# Modulo_de_isola_o_AC.net
KiCad netlist of a schematic drawn in Altium Designer
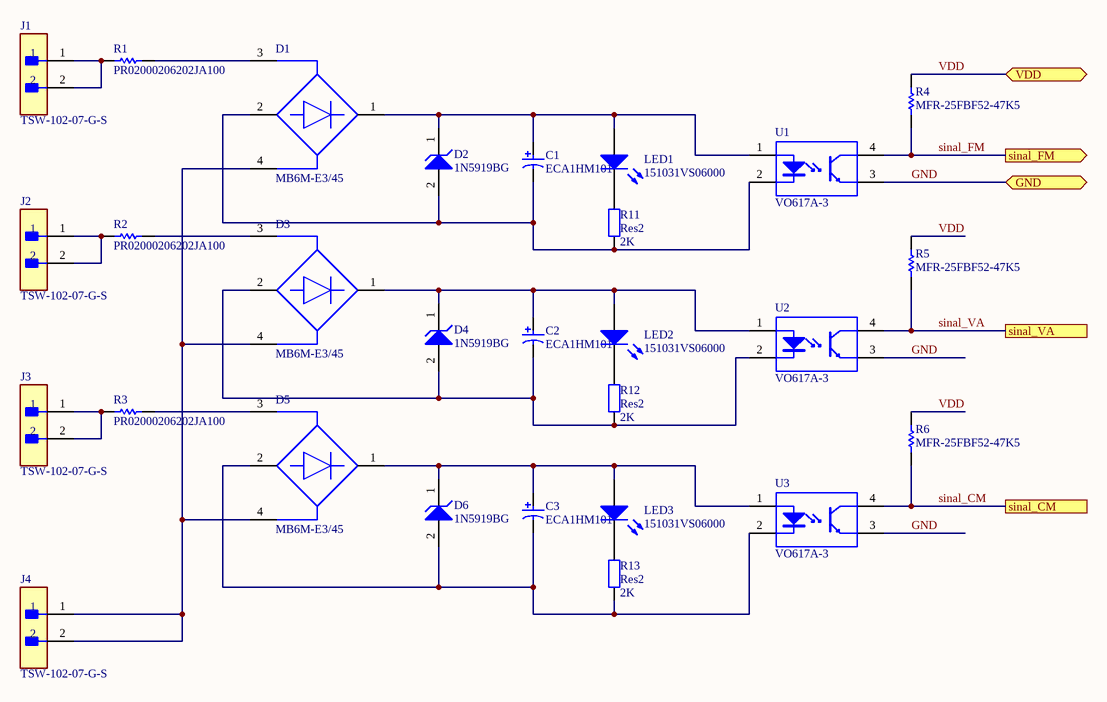
[diagram p0: Modulo de isolação AC.SchDoc]

(export (version "E")
  (design (tool "Eeschema 10.0.6"))
  (components
    (comp (ref "C1")
      (value "ECA1HM101")
      (footprint "CAPPR65-350-1150X800X1250")
      (description "Aluminum Electrolytic Capacitor, 100 uF, +/- 20%, 50 V, -40 to 85 degC, 2-Pin THD, RoHS, Bulk")
      (fields (field (name "MANUFACTURER") "Panasonic") (field (name "VOLTAGE") "50V"))
      (libsource (lib "Altium Content Vault") (part "CAP-P-2"))
    )
    (comp (ref "C2")
      (value "ECA1HM101")
      (footprint "CAPPR65-350-1150X800X1250")
      (description "Aluminum Electrolytic Capacitor, 100 uF, +/- 20%, 50 V, -40 to 85 degC, 2-Pin THD, RoHS, Bulk")
      (fields (field (name "MANUFACTURER") "Panasonic") (field (name "VOLTAGE") "50V"))
      (libsource (lib "Altium Content Vault") (part "CAP-P-2"))
    )
    (comp (ref "C3")
      (value "ECA1HM101")
      (footprint "CAPPR65-350-1150X800X1250")
      (description "Aluminum Electrolytic Capacitor, 100 uF, +/- 20%, 50 V, -40 to 85 degC, 2-Pin THD, RoHS, Bulk")
      (fields (field (name "MANUFACTURER") "Panasonic") (field (name "VOLTAGE") "50V"))
      (libsource (lib "Altium Content Vault") (part "CAP-P-2"))
    )
    (comp (ref "D1")
      (value "MB6M-E3/45")
      (footprint "FP-MB6M-E3-45-MFG")
      (description "BRIDGE RECT 1P 600V 500MA MBM")
      (libsource (lib "Altium Content Vault") (part "8d9836cf8c3bf52151cda99db45db6a"))
    )
    (comp (ref "D2")
      (value "1N5919BG")
      (footprint "ONSC-AXIAL_LEAD-2-59-10_P")
      (description "3 W Zener Voltage Regulator, 2-Pin Axial_Lead, Pb-Free, Bulk Box")
      (fields (field (name "MANUFACTURER") "On Semiconductor"))
      (libsource (lib "Altium Content Vault") (part "ONSC-K1A2-2"))
    )
    (comp (ref "D3")
      (value "MB6M-E3/45")
      (footprint "FP-MB6M-E3-45-MFG")
      (description "BRIDGE RECT 1P 600V 500MA MBM")
      (libsource (lib "Altium Content Vault") (part "8d9836cf8c3bf52151cda99db45db6a"))
    )
    (comp (ref "D4")
      (value "1N5919BG")
      (footprint "ONSC-AXIAL_LEAD-2-59-10_P")
      (description "3 W Zener Voltage Regulator, 2-Pin Axial_Lead, Pb-Free, Bulk Box")
      (fields (field (name "MANUFACTURER") "On Semiconductor"))
      (libsource (lib "Altium Content Vault") (part "ONSC-K1A2-2"))
    )
    (comp (ref "D5")
      (value "MB6M-E3/45")
      (footprint "FP-MB6M-E3-45-MFG")
      (description "BRIDGE RECT 1P 600V 500MA MBM")
      (libsource (lib "Altium Content Vault") (part "8d9836cf8c3bf52151cda99db45db6a"))
    )
    (comp (ref "D6")
      (value "1N5919BG")
      (footprint "ONSC-AXIAL_LEAD-2-59-10_P")
      (description "3 W Zener Voltage Regulator, 2-Pin Axial_Lead, Pb-Free, Bulk Box")
      (fields (field (name "MANUFACTURER") "On Semiconductor"))
      (libsource (lib "Altium Content Vault") (part "ONSC-K1A2-2"))
    )
    (comp (ref "J1")
      (value "TSW-102-07-G-S")
      (footprint "FP-TSW-102-07-G-S-MFG")
      (description "CONN HEADER VERT 2POS 2.54MM")
      (fields
        (field (name "MANUFACTURER") "Samtec")
        (field (name "OCTOPART") "https://octopart.com/tsw-102-07-g-s-samtec-272197")
      )
      (libsource (lib "Altium Content Vault") (part "3bc925449376181038e59eaffc5286c"))
    )
    (comp (ref "J2")
      (value "TSW-102-07-G-S")
      (footprint "FP-TSW-102-07-G-S-MFG")
      (description "CONN HEADER VERT 2POS 2.54MM")
      (fields
        (field (name "MANUFACTURER") "Samtec")
        (field (name "OCTOPART") "https://octopart.com/tsw-102-07-g-s-samtec-272197")
      )
      (libsource (lib "Altium Content Vault") (part "3bc925449376181038e59eaffc5286c"))
    )
    (comp (ref "J3")
      (value "TSW-102-07-G-S")
      (footprint "FP-TSW-102-07-G-S-MFG")
      (description "CONN HEADER VERT 2POS 2.54MM")
      (fields
        (field (name "MANUFACTURER") "Samtec")
        (field (name "OCTOPART") "https://octopart.com/tsw-102-07-g-s-samtec-272197")
      )
      (libsource (lib "Altium Content Vault") (part "3bc925449376181038e59eaffc5286c"))
    )
    (comp (ref "J4")
      (value "TSW-102-07-G-S")
      (footprint "FP-TSW-102-07-G-S-MFG")
      (description "CONN HEADER VERT 2POS 2.54MM")
      (fields
        (field (name "MANUFACTURER") "Samtec")
        (field (name "OCTOPART") "https://octopart.com/tsw-102-07-g-s-samtec-272197")
      )
      (libsource (lib "Altium Content Vault") (part "3bc925449376181038e59eaffc5286c"))
    )
    (comp (ref "LED1")
      (value "151031VS06000")
      (footprint "Type 3mm")
      (description "THT LED round mono-color color lens, WL-TMRC , Bright Green")
      (fields (field (name "MANUFACTURER") "Wuerth Elektronik"))
      (libsource (lib "Altium Content Vault") (part "WE-LED_K1A2-2"))
    )
    (comp (ref "LED2")
      (value "151031VS06000")
      (footprint "Type 3mm")
      (description "THT LED round mono-color color lens, WL-TMRC , Bright Green")
      (fields (field (name "MANUFACTURER") "Wuerth Elektronik"))
      (libsource (lib "Altium Content Vault") (part "WE-LED_K1A2-2"))
    )
    (comp (ref "LED3")
      (value "151031VS06000")
      (footprint "Type 3mm")
      (description "THT LED round mono-color color lens, WL-TMRC , Bright Green")
      (fields (field (name "MANUFACTURER") "Wuerth Elektronik"))
      (libsource (lib "Altium Content Vault") (part "WE-LED_K1A2-2"))
    )
    (comp (ref "R1")
      (value "PR02000206202JA100")
      (footprint "VISH-A1-2_V2")
      (description "Power Metal Film Leaded Resistor, 62 KOhm +/-5%, 2 W, 2-Pin THD, RoHS, Ammo Pack")
      (fields (field (name "TOLERANCE") "+/-5%") (field (name "POWER") "2 W"))
      (libsource (lib "Altium Content Vault") (part "VISH-RES-2"))
    )
    (comp (ref "R2")
      (value "PR02000206202JA100")
      (footprint "VISH-A1-2_V2")
      (description "Power Metal Film Leaded Resistor, 62 KOhm +/-5%, 2 W, 2-Pin THD, RoHS, Ammo Pack")
      (fields (field (name "TOLERANCE") "+/-5%") (field (name "POWER") "2 W"))
      (libsource (lib "Altium Content Vault") (part "VISH-RES-2"))
    )
    (comp (ref "R3")
      (value "PR02000206202JA100")
      (footprint "VISH-A1-2_V2")
      (description "Power Metal Film Leaded Resistor, 62 KOhm +/-5%, 2 W, 2-Pin THD, RoHS, Ammo Pack")
      (fields (field (name "TOLERANCE") "+/-5%") (field (name "POWER") "2 W"))
      (libsource (lib "Altium Content Vault") (part "VISH-RES-2"))
    )
    (comp (ref "R4")
      (value "MFR-25FBF52-47K5")
      (footprint "RESA60-630X240")
      (description "Axial Resistor, 47.5 KOhm, +/- 1%, 0.25 W, -55 to 155 degC, 2-Pin THD, RoHS, Bulk")
      (fields (field (name "TOLERANCE") "20%"))
      (libsource (lib "Altium Content Vault") (part "RES-2"))
    )
    (comp (ref "R5")
      (value "MFR-25FBF52-47K5")
      (footprint "RESA60-630X240")
      (description "Axial Resistor, 47.5 KOhm, +/- 1%, 0.25 W, -55 to 155 degC, 2-Pin THD, RoHS, Bulk")
      (fields (field (name "TOLERANCE") "20%"))
      (libsource (lib "Altium Content Vault") (part "RES-2"))
    )
    (comp (ref "R6")
      (value "MFR-25FBF52-47K5")
      (footprint "RESA60-630X240")
      (description "Axial Resistor, 47.5 KOhm, +/- 1%, 0.25 W, -55 to 155 degC, 2-Pin THD, RoHS, Bulk")
      (fields (field (name "TOLERANCE") "20%"))
      (libsource (lib "Altium Content Vault") (part "RES-2"))
    )
    (comp (ref "R11")
      (value "Res2")
      (footprint "AXIAL-0.4")
      (description "Resistor")
      (fields (field (name "ALTIUM_VALUE") "2K") (field (name "PUBLISHER") "Altium Limited"))
      (libsource (lib "Miscellaneous Devices") (part "Res2"))
    )
    (comp (ref "R12")
      (value "Res2")
      (footprint "AXIAL-0.4")
      (description "Resistor")
      (fields (field (name "ALTIUM_VALUE") "2K") (field (name "PUBLISHER") "Altium Limited"))
      (libsource (lib "Miscellaneous Devices") (part "Res2"))
    )
    (comp (ref "R13")
      (value "Res2")
      (footprint "AXIAL-0.4")
      (description "Resistor")
      (fields (field (name "ALTIUM_VALUE") "2K") (field (name "PUBLISHER") "Altium Limited"))
      (libsource (lib "Miscellaneous Devices") (part "Res2"))
    )
    (comp (ref "U1")
      (value "VO617A-3")
      (footprint "VISH-DIP-4")
      (fields (field (name "MANUFACTURER") "Vishay/Semiconductor"))
      (libsource (lib "Altium Content Vault") (part "OPTO-AKEC-4"))
    )
    (comp (ref "U2")
      (value "VO617A-3")
      (footprint "VISH-DIP-4")
      (fields (field (name "MANUFACTURER") "Vishay/Semiconductor"))
      (libsource (lib "Altium Content Vault") (part "OPTO-AKEC-4"))
    )
    (comp (ref "U3")
      (value "VO617A-3")
      (footprint "VISH-DIP-4")
      (fields (field (name "MANUFACTURER") "Vishay/Semiconductor"))
      (libsource (lib "Altium Content Vault") (part "OPTO-AKEC-4"))
    )
  )
  (nets
    (net (code "1") (name "/GND") (class "Default")
      (node (ref "U1") (pin "3") (pinfunction "EMITTER_3") (pintype "passive"))
      (node (ref "U2") (pin "3") (pinfunction "EMITTER_3") (pintype "passive"))
      (node (ref "U3") (pin "3") (pinfunction "EMITTER_3") (pintype "passive"))
    )
    (net (code "2") (name "/VDD") (class "Default")
      (node (ref "R4") (pin "2") (pinfunction "2_2") (pintype "passive"))
      (node (ref "R5") (pin "2") (pinfunction "2_2") (pintype "passive"))
      (node (ref "R6") (pin "2") (pinfunction "2_2") (pintype "passive"))
    )
    (net (code "3") (name "/sinal_CM") (class "Default")
      (node (ref "R6") (pin "1") (pinfunction "1_1") (pintype "passive"))
      (node (ref "U3") (pin "4") (pinfunction "COLLECTOR_4") (pintype "passive"))
    )
    (net (code "4") (name "/sinal_FM") (class "Default")
      (node (ref "R4") (pin "1") (pinfunction "1_1") (pintype "passive"))
      (node (ref "U1") (pin "4") (pinfunction "COLLECTOR_4") (pintype "passive"))
    )
    (net (code "5") (name "/sinal_VA") (class "Default")
      (node (ref "R5") (pin "1") (pinfunction "1_1") (pintype "passive"))
      (node (ref "U2") (pin "4") (pinfunction "COLLECTOR_4") (pintype "passive"))
    )
    (net (code "6") (name "Net-(D1-+)") (class "Default")
      (node (ref "C1") (pin "1") (pinfunction "1_1") (pintype "passive"))
      (node (ref "D1") (pin "1") (pinfunction "+_1") (pintype "passive"))
      (node (ref "D2") (pin "1") (pinfunction "K_1") (pintype "passive"))
      (node (ref "LED1") (pin "2") (pinfunction "A_2") (pintype "passive"))
      (node (ref "U1") (pin "1") (pinfunction "ANODE_1") (pintype "passive"))
    )
    (net (code "7") (name "Net-(D1--)") (class "Default")
      (node (ref "C1") (pin "2") (pinfunction "2_2") (pintype "passive"))
      (node (ref "D1") (pin "2") (pinfunction "-_2") (pintype "passive"))
      (node (ref "D2") (pin "2") (pinfunction "A_2") (pintype "passive"))
      (node (ref "R11") (pin "1") (pinfunction "1_1") (pintype "passive"))
      (node (ref "U1") (pin "2") (pinfunction "CATHODE_2") (pintype "passive"))
    )
    (net (code "8") (name "Net-(D1-1_~)") (class "Default")
      (node (ref "D1") (pin "3") (pinfunction "1_~_3") (pintype "passive"))
      (node (ref "R1") (pin "2") (pinfunction "2_2") (pintype "passive"))
    )
    (net (code "9") (name "Net-(D1-2_~)") (class "Default")
      (node (ref "D1") (pin "4") (pinfunction "2_~_4") (pintype "passive"))
      (node (ref "D3") (pin "4") (pinfunction "2_~_4") (pintype "passive"))
      (node (ref "D5") (pin "4") (pinfunction "2_~_4") (pintype "passive"))
      (node (ref "J4") (pin "1") (pinfunction "1_1") (pintype "passive"))
      (node (ref "J4") (pin "2") (pinfunction "2_2") (pintype "passive"))
    )
    (net (code "10") (name "Net-(D3-+)") (class "Default")
      (node (ref "C2") (pin "1") (pinfunction "1_1") (pintype "passive"))
      (node (ref "D3") (pin "1") (pinfunction "+_1") (pintype "passive"))
      (node (ref "D4") (pin "1") (pinfunction "K_1") (pintype "passive"))
      (node (ref "LED2") (pin "2") (pinfunction "A_2") (pintype "passive"))
      (node (ref "U2") (pin "1") (pinfunction "ANODE_1") (pintype "passive"))
    )
    (net (code "11") (name "Net-(D3--)") (class "Default")
      (node (ref "C2") (pin "2") (pinfunction "2_2") (pintype "passive"))
      (node (ref "D3") (pin "2") (pinfunction "-_2") (pintype "passive"))
      (node (ref "D4") (pin "2") (pinfunction "A_2") (pintype "passive"))
      (node (ref "R12") (pin "1") (pinfunction "1_1") (pintype "passive"))
      (node (ref "U2") (pin "2") (pinfunction "CATHODE_2") (pintype "passive"))
    )
    (net (code "12") (name "Net-(D3-1_~)") (class "Default")
      (node (ref "D3") (pin "3") (pinfunction "1_~_3") (pintype "passive"))
      (node (ref "R2") (pin "2") (pinfunction "2_2") (pintype "passive"))
    )
    (net (code "13") (name "Net-(D5-+)") (class "Default")
      (node (ref "C3") (pin "1") (pinfunction "1_1") (pintype "passive"))
      (node (ref "D5") (pin "1") (pinfunction "+_1") (pintype "passive"))
      (node (ref "D6") (pin "1") (pinfunction "K_1") (pintype "passive"))
      (node (ref "LED3") (pin "2") (pinfunction "A_2") (pintype "passive"))
      (node (ref "U3") (pin "1") (pinfunction "ANODE_1") (pintype "passive"))
    )
    (net (code "14") (name "Net-(D5--)") (class "Default")
      (node (ref "C3") (pin "2") (pinfunction "2_2") (pintype "passive"))
      (node (ref "D5") (pin "2") (pinfunction "-_2") (pintype "passive"))
      (node (ref "D6") (pin "2") (pinfunction "A_2") (pintype "passive"))
      (node (ref "R13") (pin "1") (pinfunction "1_1") (pintype "passive"))
      (node (ref "U3") (pin "2") (pinfunction "CATHODE_2") (pintype "passive"))
    )
    (net (code "15") (name "Net-(D5-1_~)") (class "Default")
      (node (ref "D5") (pin "3") (pinfunction "1_~_3") (pintype "passive"))
      (node (ref "R3") (pin "2") (pinfunction "2_2") (pintype "passive"))
    )
    (net (code "16") (name "Net-(J1-Pad1)") (class "Default")
      (node (ref "J1") (pin "1") (pinfunction "1_1") (pintype "passive"))
      (node (ref "J1") (pin "2") (pinfunction "2_2") (pintype "passive"))
      (node (ref "R1") (pin "1") (pinfunction "1_1") (pintype "passive"))
    )
    (net (code "17") (name "Net-(J2-Pad1)") (class "Default")
      (node (ref "J2") (pin "1") (pinfunction "1_1") (pintype "passive"))
      (node (ref "J2") (pin "2") (pinfunction "2_2") (pintype "passive"))
      (node (ref "R2") (pin "1") (pinfunction "1_1") (pintype "passive"))
    )
    (net (code "18") (name "Net-(J3-Pad1)") (class "Default")
      (node (ref "J3") (pin "1") (pinfunction "1_1") (pintype "passive"))
      (node (ref "J3") (pin "2") (pinfunction "2_2") (pintype "passive"))
      (node (ref "R3") (pin "1") (pinfunction "1_1") (pintype "passive"))
    )
    (net (code "19") (name "Net-(LED1-K)") (class "Default")
      (node (ref "LED1") (pin "1") (pinfunction "K_1") (pintype "passive"))
      (node (ref "R11") (pin "2") (pinfunction "2_2") (pintype "passive"))
    )
    (net (code "20") (name "Net-(LED2-K)") (class "Default")
      (node (ref "LED2") (pin "1") (pinfunction "K_1") (pintype "passive"))
      (node (ref "R12") (pin "2") (pinfunction "2_2") (pintype "passive"))
    )
    (net (code "21") (name "Net-(LED3-K)") (class "Default")
      (node (ref "LED3") (pin "1") (pinfunction "K_1") (pintype "passive"))
      (node (ref "R13") (pin "2") (pinfunction "2_2") (pintype "passive"))
    )
  )
)
